# HT_L293D_Driver.net
KiCad netlist of a schematic drawn in Altium Designer
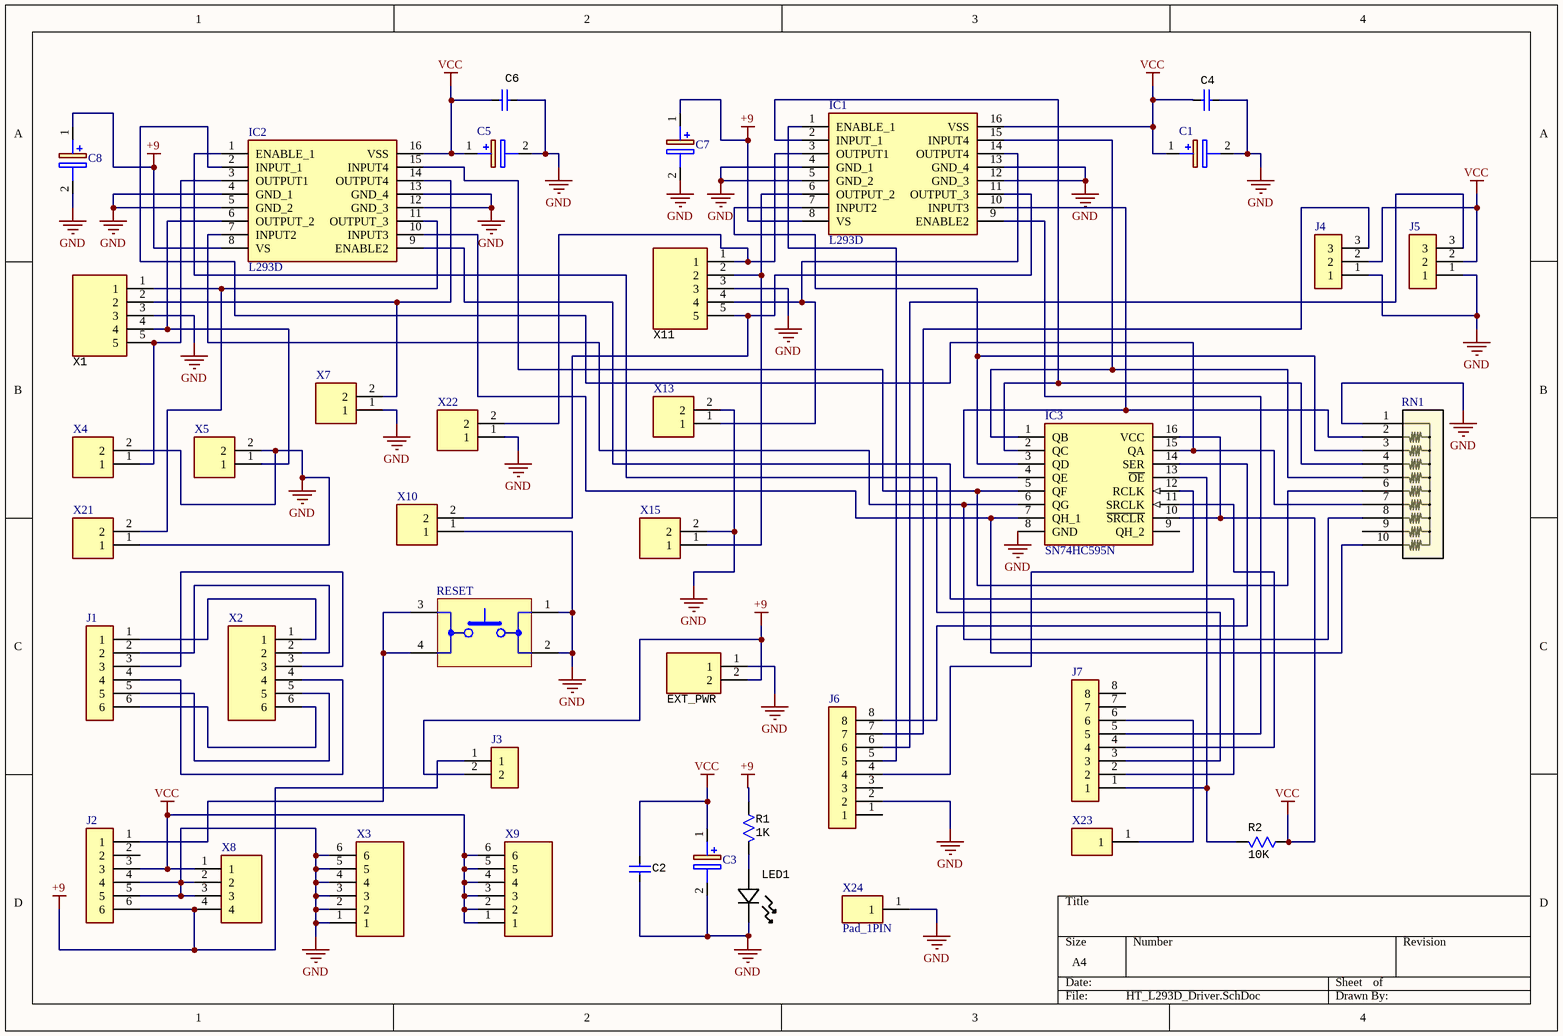
[diagram p0: HT_L293D_Driver.SchDoc]

(export (version "E")
  (design (tool "Eeschema 10.0.6"))
  (components
    (comp (ref "C1")
      (value "Aluminum_Electrolytic_Capacitor")
      (footprint "Aluminum_Electrolytic_Capacitor")
      (description "Capacitor Polarised")
      (fields (field (name "MANUFACTURER_PART_NUMBER") "EKY-350ETC221MH15D") (field (name "VOLTAGE") "100uF"))
      (libsource (lib "") (part "Aluminum_Electrolytic_Capacitor_1"))
    )
    (comp (ref "C2")
      (value "~")
      (footprint "CERAMIC_CAPACITOR_0.1uF")
      (fields
        (field (name "MANUFACTURER") "Epcos")
        (field (name "PARTNUMBER") "B32774D4106K000")
        (field (name "VALUEMANUFACTURERPARTNUMBER") "Film capacitor, 10μF, 450VDC, ±10%, 10.9mOhm, 31.5x15 mm, -40...+105°C")
      )
      (libsource (lib "MyL293D") (part "Ceramic_Capacitor"))
    )
    (comp (ref "C3")
      (value "Aluminum_Electrolytic_Capacitor")
      (footprint "Aluminum_Electrolytic_Capacitor")
      (description "Capacitor Polarised")
      (fields (field (name "MANUFACTURER_PART_NUMBER") "EKY-350ETC221MH15D") (field (name "VOLTAGE") "16VDC"))
      (libsource (lib "MyL293D") (part "Aluminum_Electrolytic_Capacitor"))
    )
    (comp (ref "C4")
      (value "~")
      (footprint "CERAMIC_CAPACITOR_0.1uF")
      (description "Capacitor Non Polarised")
      (fields (field (name "MANUFACTURER") "Epcos") (field (name "PARTNUMBER") "B32774D4106K000"))
      (libsource (lib "MyL293D") (part "Ceramic_Capacitor"))
    )
    (comp (ref "C5")
      (value "Aluminum_Electrolytic_Capacitor")
      (footprint "Aluminum_Electrolytic_Capacitor")
      (description "Capacitor Polarised")
      (fields (field (name "MANUFACTURER_PART_NUMBER") "EKY-350ETC221MH15D") (field (name "VOLTAGE") "16VDC"))
      (libsource (lib "") (part "Aluminum_Electrolytic_Capacitor_1"))
    )
    (comp (ref "C6")
      (value "~")
      (footprint "CERAMIC_CAPACITOR_0.1uF")
      (fields
        (field (name "MANUFACTURER") "Epcos")
        (field (name "PARTNUMBER") "B32774D4106K000")
        (field (name "VALUEMANUFACTURERPARTNUMBER") "Film capacitor, 0.1μF, 450VDC, ±10%, 10.9mOhm, 31.5x15 mm, -40...+105°C")
      )
      (libsource (lib "MyL293D") (part "Ceramic_Capacitor"))
    )
    (comp (ref "C7")
      (value "Aluminum_Electrolytic_Capacitor")
      (footprint "Aluminum_Electrolytic_Capacitor")
      (description "Capacitor Polarised")
      (fields (field (name "MANUFACTURER_PART_NUMBER") "EKY-350ETC221MH15D") (field (name "VOLTAGE") "16VDC"))
      (libsource (lib "MyL293D") (part "Aluminum_Electrolytic_Capacitor"))
    )
    (comp (ref "C8")
      (value "Aluminum_Electrolytic_Capacitor")
      (footprint "Aluminum_Electrolytic_Capacitor")
      (description "Capacitor Polarised")
      (fields (field (name "MANUFACTURER_PART_NUMBER") "EKY-350ETC221MH15D") (field (name "VOLTAGE") "16VDC"))
      (libsource (lib "MyL293D") (part "Aluminum_Electrolytic_Capacitor"))
    )
    (comp (ref "EXT_PWR")
      (value "~")
      (footprint "Terminal_Block_2PIN")
      (fields
        (field (name "MANUFACTURER") "Degson")
        (field (name "VALUEMANUFACTURERPARTNUMBER") "Terminal connector, 2pin, 3.5mm, 300VAC, 10A")
        (field (name "PARTNUMBER") "DG350-3.5-02P-14")
      )
      (libsource (lib "MyL293D") (part "Terminal_Block_2PIN"))
    )
    (comp (ref "IC1")
      (value "L293D")
      (footprint "L293D_WITH_DIP16")
      (description "Integrated Circuit")
      (fields (field (name "MOUSER PART NUMBER") "511-L293D"))
      (libsource (lib "MyL293D") (part "L293D"))
    )
    (comp (ref "IC2")
      (value "L293D")
      (footprint "L293D_WITH_DIP16")
      (description "Integrated Circuit")
      (fields (field (name "MOUSER PART NUMBER") "511-L293D"))
      (libsource (lib "MyL293D") (part "L293D"))
    )
    (comp (ref "IC3")
      (value "SN74HC595N")
      (footprint "L293D_WITH_DIP16")
      (description "Integrated Circuit")
      (fields (field (name "MOUSER PART NUMBER") "595-SN74HC595N"))
      (libsource (lib "MyL293D") (part "SN74HC595N"))
    )
    (comp (ref "J1")
      (value "Headers_6PIN")
      (footprint "HEADERS_6PIN")
      (fields (field (name "MF") "{'manufacturer': u'TE Connectivity'}") (field (name "MP") "87227-3"))
      (libsource (lib "MyL293D") (part "Headers_6PIN"))
    )
    (comp (ref "J2")
      (value "Headers_6PIN")
      (footprint "HEADERS_6PIN")
      (fields (field (name "MF") "{'manufacturer': u'TE Connectivity'}") (field (name "MP") "87227-3"))
      (libsource (lib "MyL293D") (part "Headers_6PIN"))
    )
    (comp (ref "J3")
      (value "Headers_2PIN")
      (footprint "HEADERS_2PIN")
      (fields (field (name "MF") "{'manufacturer': u'TE Connectivity'}") (field (name "MP") "87227-3"))
      (libsource (lib "MyL293D") (part "Headers_2PIN"))
    )
    (comp (ref "J4")
      (value "Headers_3PIN")
      (footprint "HEADERS_3PIN")
      (fields (field (name "MF") "{'manufacturer': u'TE Connectivity'}") (field (name "MP") "87227-3"))
      (libsource (lib "MyL293D") (part "Headers_3PIN"))
    )
    (comp (ref "J5")
      (value "Headers_3PIN")
      (footprint "HEADERS_3PIN")
      (fields (field (name "MF") "{'manufacturer': u'TE Connectivity'}") (field (name "MP") "87227-3"))
      (libsource (lib "MyL293D") (part "Headers_3PIN"))
    )
    (comp (ref "J6")
      (value "Headers_8PIN")
      (footprint "HEADERS_8PIN")
      (fields (field (name "MF") "{'manufacturer': u'TE Connectivity'}") (field (name "MP") "87227-3"))
      (libsource (lib "MyL293D") (part "Headers_8PIN"))
    )
    (comp (ref "J7")
      (value "Headers_8PIN")
      (footprint "HEADERS_8PIN")
      (fields (field (name "MF") "{'manufacturer': u'TE Connectivity'}") (field (name "MP") "87227-3"))
      (libsource (lib "MyL293D") (part "Headers_8PIN"))
    )
    (comp (ref "LED1")
      (value "~")
      (footprint "Green_LED_3mm")
      (fields (field (name "VALUEMANUFACTURERPARTNUMBER") "LED, Green, *, *, *, -55...+150°C"))
      (libsource (lib "MyL293D") (part "Green_LED_3mm"))
    )
    (comp (ref "R1")
      (value "1K")
      (footprint "RESISTOR_TH_1K")
      (fields
        (field (name "MANUFACTURER") "Yageo")
        (field (name "PARTNUMBER") "RC0201JR-07100RL")
        (field (name "VALUEMANUFACTURERPARTNUMBER") "Resistor film, 1K, , 0201, 0.05W, -55...+125°C")
      )
      (libsource (lib "MyL293D") (part "Resistor_1K"))
    )
    (comp (ref "R2")
      (value "10K")
      (footprint "RESISTOR_TH_10K")
      (fields
        (field (name "MANUFACTURER") "Yageo")
        (field (name "PARTNUMBER") "RC0201JR-07100RL")
        (field (name "VALUEMANUFACTURERPARTNUMBER") "Resistor film, 10K, , 0201, 0.05W, -55...+125°C")
      )
      (libsource (lib "MyL293D") (part "Resistor_10K"))
    )
    (comp (ref "RESET")
      (value "1825910-6")
      (footprint "1825910-6")
      (description "SWITCH TACTILE SPST-NO 0.05A 24V")
      (fields
        (field (name "MANUFACTURER") "TE Connectivity")
        (field (name ".CREATOR") "MM")
        (field (name ".CHECKED PCB") "RF")
        (field (name ".CHECKED SCH") "RF")
      )
      (libsource (lib "MyL293D") (part "Button_Reset"))
    )
    (comp (ref "RN1")
      (value "Resistor_Network_10K")
      (footprint "RESISTOR_NETWORK_10K")
      (libsource (lib "MyL293D") (part "Resistor_Network_10K"))
    )
    (comp (ref "X1")
      (value "~")
      (footprint "TERMINAL_BLOCK_5PIN")
      (fields
        (field (name "MANUFACTURER") "Degson")
        (field (name "VALUEMANUFACTURERPARTNUMBER") "Terminal connector, 3pin, 3.5mm, 300VAC, 10A")
        (field (name "PARTNUMBER") "DG350-3.5-03P-14")
      )
      (libsource (lib "MyL293D") (part "Terminal_Block_5PIN"))
    )
    (comp (ref "X2") (value "Pad_6PIN") (footprint "PAD_6PIN") (libsource (lib "") (part "Pad_6PIN_1")))
    (comp (ref "X3") (value "Pad_6PIN") (footprint "PAD_6PIN") (libsource (lib "MyL293D") (part "Pad_6PIN")))
    (comp (ref "X4") (value "Pad_2PIN") (footprint "PAD_2PIN") (libsource (lib "MyL293D") (part "Pad_2PIN")))
    (comp (ref "X5") (value "Pad_2PIN") (footprint "PAD_2PIN") (libsource (lib "MyL293D") (part "Pad_2PIN")))
    (comp (ref "X7") (value "Pad_2PIN") (footprint "PAD_2PIN") (libsource (lib "MyL293D") (part "Pad_2PIN")))
    (comp (ref "X8") (value "Pad_4PIN") (footprint "PAD_4PIN") (libsource (lib "MyL293D") (part "Pad_4PIN")))
    (comp (ref "X9") (value "Pad_6PIN") (footprint "PAD_6PIN") (libsource (lib "MyL293D") (part "Pad_6PIN")))
    (comp (ref "X10") (value "Pad_2PIN") (footprint "PAD_2PIN") (libsource (lib "MyL293D") (part "Pad_2PIN")))
    (comp (ref "X11")
      (value "~")
      (footprint "TERMINAL_BLOCK_5PIN")
      (fields
        (field (name "MANUFACTURER") "Degson")
        (field (name "VALUEMANUFACTURERPARTNUMBER") "Terminal connector, 3pin, 3.5mm, 300VAC, 10A")
        (field (name "PARTNUMBER") "DG350-3.5-03P-14")
      )
      (libsource (lib "MyL293D") (part "Terminal_Block_5PIN"))
    )
    (comp (ref "X13") (value "Pad_2PIN") (footprint "PAD_2PIN") (libsource (lib "MyL293D") (part "Pad_2PIN")))
    (comp (ref "X15") (value "Pad_2PIN") (footprint "PAD_2PIN") (libsource (lib "MyL293D") (part "Pad_2PIN")))
    (comp (ref "X21") (value "Pad_2PIN") (footprint "PAD_2PIN") (libsource (lib "MyL293D") (part "Pad_2PIN")))
    (comp (ref "X22") (value "Pad_2PIN") (footprint "PAD_2PIN") (libsource (lib "MyL293D") (part "Pad_2PIN")))
    (comp (ref "X23") (value "Pad_1PIN") (footprint "PAD_1PIN") (libsource (lib "MyL293D") (part "Pad_1PIN")))
    (comp (ref "X24") (value "Pad_1PIN") (footprint "PAD_1PIN") (libsource (lib "MyL293D") (part "Pad_1PIN")))
  )
  (nets
    (net (code "1") (name "+9") (class "Default")
      (node (ref "C7") (pin "1") (pinfunction "+_1") (pintype "passive"))
      (node (ref "C8") (pin "1") (pinfunction "+_1") (pintype "passive"))
      (node (ref "EXT_PWR") (pin "2") (pinfunction "2_2") (pintype "passive"))
      (node (ref "IC1") (pin "8") (pinfunction "VS_8") (pintype "passive"))
      (node (ref "IC2") (pin "8") (pinfunction "VS_8") (pintype "passive"))
      (node (ref "J2") (pin "6") (pinfunction "6_6") (pintype "passive"))
      (node (ref "J3") (pin "1") (pinfunction "1_1") (pintype "passive"))
      (node (ref "J3") (pin "2") (pinfunction "2_2") (pintype "passive"))
      (node (ref "R1") (pin "1") (pinfunction "1_1") (pintype "passive"))
      (node (ref "X8") (pin "4") (pinfunction "4_4") (pintype "passive"))
    )
    (net (code "2") (name "GND") (class "Default")
      (node (ref "C1") (pin "2") (pinfunction "-_2") (pintype "passive"))
      (node (ref "C2") (pin "2") (pinfunction "2_2") (pintype "passive"))
      (node (ref "C3") (pin "2") (pinfunction "-_2") (pintype "passive"))
      (node (ref "C4") (pin "2") (pinfunction "2_2") (pintype "passive"))
      (node (ref "C5") (pin "2") (pinfunction "-_2") (pintype "passive"))
      (node (ref "C6") (pin "2") (pinfunction "2_2") (pintype "passive"))
      (node (ref "C7") (pin "2") (pinfunction "-_2") (pintype "passive"))
      (node (ref "C8") (pin "2") (pinfunction "-_2") (pintype "passive"))
      (node (ref "EXT_PWR") (pin "1") (pinfunction "1_1") (pintype "passive"))
      (node (ref "IC1") (pin "12") (pinfunction "GND_3_12") (pintype "passive"))
      (node (ref "IC1") (pin "13") (pinfunction "GND_4_13") (pintype "passive"))
      (node (ref "IC1") (pin "4") (pinfunction "GND_1_4") (pintype "passive"))
      (node (ref "IC1") (pin "5") (pinfunction "GND_2_5") (pintype "passive"))
      (node (ref "IC2") (pin "12") (pinfunction "GND_3_12") (pintype "passive"))
      (node (ref "IC2") (pin "13") (pinfunction "GND_4_13") (pintype "passive"))
      (node (ref "IC2") (pin "4") (pinfunction "GND_1_4") (pintype "passive"))
      (node (ref "IC2") (pin "5") (pinfunction "GND_2_5") (pintype "passive"))
      (node (ref "IC3") (pin "8") (pinfunction "GND_8") (pintype "power_in"))
      (node (ref "J2") (pin "4") (pinfunction "4_4") (pintype "passive"))
      (node (ref "J2") (pin "5") (pinfunction "5_5") (pintype "passive"))
      (node (ref "J4") (pin "1") (pinfunction "1_1") (pintype "passive"))
      (node (ref "J5") (pin "1") (pinfunction "1_1") (pintype "passive"))
      (node (ref "J6") (pin "2") (pinfunction "2_2") (pintype "passive"))
      (node (ref "LED1") (pin "1") (pinfunction "1_1") (pintype "passive"))
      (node (ref "RESET") (pin "1") (pinfunction "1_1") (pintype "passive"))
      (node (ref "RESET") (pin "2") (pinfunction "2_2") (pintype "passive"))
      (node (ref "RN1") (pin "1") (pinfunction "1_1") (pintype "passive"))
      (node (ref "X1") (pin "3") (pinfunction "3_3") (pintype "passive"))
      (node (ref "X10") (pin "1") (pinfunction "1_1") (pintype "passive"))
      (node (ref "X11") (pin "3") (pinfunction "3_3") (pintype "passive"))
      (node (ref "X13") (pin "2") (pinfunction "2_2") (pintype "passive"))
      (node (ref "X15") (pin "2") (pinfunction "2_2") (pintype "passive"))
      (node (ref "X21") (pin "1") (pinfunction "1_1") (pintype "passive"))
      (node (ref "X22") (pin "1") (pinfunction "1_1") (pintype "passive"))
      (node (ref "X24") (pin "1") (pinfunction "1_1") (pintype "passive"))
      (node (ref "X3") (pin "1") (pinfunction "1_1") (pintype "passive"))
      (node (ref "X3") (pin "2") (pinfunction "2_2") (pintype "passive"))
      (node (ref "X3") (pin "3") (pinfunction "3_3") (pintype "passive"))
      (node (ref "X3") (pin "4") (pinfunction "4_4") (pintype "passive"))
      (node (ref "X3") (pin "5") (pinfunction "5_5") (pintype "passive"))
      (node (ref "X3") (pin "6") (pinfunction "6_6") (pintype "passive"))
      (node (ref "X4") (pin "2") (pinfunction "2_2") (pintype "passive"))
      (node (ref "X5") (pin "2") (pinfunction "2_2") (pintype "passive"))
      (node (ref "X7") (pin "1") (pinfunction "1_1") (pintype "passive"))
      (node (ref "X8") (pin "2") (pinfunction "2_2") (pintype "passive"))
      (node (ref "X8") (pin "3") (pinfunction "3_3") (pintype "passive"))
    )
    (net (code "3") (name "Net-(IC1-ENABLE2)") (class "Default")
      (node (ref "IC1") (pin "9") (pinfunction "ENABLE2_9") (pintype "passive"))
      (node (ref "J7") (pin "5") (pinfunction "5_5") (pintype "passive"))
    )
    (net (code "4") (name "Net-(IC1-ENABLE_1)") (class "Default")
      (node (ref "IC1") (pin "1") (pinfunction "ENABLE_1_1") (pintype "passive"))
      (node (ref "J6") (pin "5") (pinfunction "5_5") (pintype "passive"))
    )
    (net (code "5") (name "Net-(IC1-INPUT2)") (class "Default")
      (node (ref "IC1") (pin "7") (pinfunction "INPUT2_7") (pintype "passive"))
      (node (ref "IC3") (pin "3") (pinfunction "QD_3") (pintype "passive"))
      (node (ref "RN1") (pin "3") (pinfunction "3_3") (pintype "passive"))
    )
    (net (code "6") (name "Net-(IC1-INPUT3)") (class "Default")
      (node (ref "IC1") (pin "10") (pinfunction "INPUT3_10") (pintype "passive"))
      (node (ref "IC3") (pin "4") (pinfunction "QE_4") (pintype "passive"))
      (node (ref "RN1") (pin "2") (pinfunction "2_2") (pintype "passive"))
    )
    (net (code "7") (name "Net-(IC1-INPUT4)") (class "Default")
      (node (ref "IC1") (pin "15") (pinfunction "INPUT4_15") (pintype "passive"))
      (node (ref "IC3") (pin "1") (pinfunction "QB_1") (pintype "passive"))
      (node (ref "RN1") (pin "5") (pinfunction "5_5") (pintype "passive"))
    )
    (net (code "8") (name "Net-(IC1-INPUT_1)") (class "Default")
      (node (ref "IC1") (pin "2") (pinfunction "INPUT_1_2") (pintype "passive"))
      (node (ref "IC3") (pin "2") (pinfunction "QC_2") (pintype "passive"))
      (node (ref "RN1") (pin "4") (pinfunction "4_4") (pintype "passive"))
    )
    (net (code "9") (name "Net-(IC1-OUTPUT1)") (class "Default")
      (node (ref "IC1") (pin "3") (pinfunction "OUTPUT1_3") (pintype "passive"))
      (node (ref "X11") (pin "1") (pinfunction "1_1") (pintype "passive"))
      (node (ref "X22") (pin "2") (pinfunction "2_2") (pintype "passive"))
    )
    (net (code "10") (name "Net-(IC1-OUTPUT4)") (class "Default")
      (node (ref "IC1") (pin "14") (pinfunction "OUTPUT4_14") (pintype "passive"))
      (node (ref "X11") (pin "4") (pinfunction "4_4") (pintype "passive"))
      (node (ref "X13") (pin "1") (pinfunction "1_1") (pintype "passive"))
    )
    (net (code "11") (name "Net-(IC1-OUTPUT_2)") (class "Default")
      (node (ref "IC1") (pin "6") (pinfunction "OUTPUT_2_6") (pintype "passive"))
      (node (ref "X11") (pin "2") (pinfunction "2_2") (pintype "passive"))
      (node (ref "X15") (pin "1") (pinfunction "1_1") (pintype "passive"))
    )
    (net (code "12") (name "Net-(IC1-OUTPUT_3)") (class "Default")
      (node (ref "IC1") (pin "11") (pinfunction "OUTPUT_3_11") (pintype "passive"))
      (node (ref "X10") (pin "2") (pinfunction "2_2") (pintype "passive"))
      (node (ref "X11") (pin "5") (pinfunction "5_5") (pintype "passive"))
    )
    (net (code "13") (name "Net-(IC2-ENABLE2)") (class "Default")
      (node (ref "IC2") (pin "9") (pinfunction "ENABLE2_9") (pintype "passive"))
      (node (ref "J7") (pin "2") (pinfunction "2_2") (pintype "passive"))
    )
    (net (code "14") (name "Net-(IC2-ENABLE_1)") (class "Default")
      (node (ref "IC2") (pin "1") (pinfunction "ENABLE_1_1") (pintype "passive"))
      (node (ref "J7") (pin "3") (pinfunction "3_3") (pintype "passive"))
    )
    (net (code "15") (name "Net-(IC2-INPUT2)") (class "Default")
      (node (ref "IC2") (pin "7") (pinfunction "INPUT2_7") (pintype "passive"))
      (node (ref "IC3") (pin "6") (pinfunction "QG_6") (pintype "passive"))
      (node (ref "RN1") (pin "8") (pinfunction "8_8") (pintype "passive"))
    )
    (net (code "16") (name "Net-(IC2-INPUT3)") (class "Default")
      (node (ref "IC2") (pin "10") (pinfunction "INPUT3_10") (pintype "passive"))
      (node (ref "IC3") (pin "7") (pinfunction "QH_1_7") (pintype "passive"))
      (node (ref "RN1") (pin "10") (pinfunction "10_10") (pintype "passive"))
    )
    (net (code "17") (name "Net-(IC2-INPUT4)") (class "Default")
      (node (ref "IC2") (pin "15") (pinfunction "INPUT4_15") (pintype "passive"))
      (node (ref "IC3") (pin "5") (pinfunction "QF_5") (pintype "passive"))
      (node (ref "RN1") (pin "6") (pinfunction "6_6") (pintype "passive"))
    )
    (net (code "18") (name "Net-(IC2-INPUT_1)") (class "Default")
      (node (ref "IC2") (pin "2") (pinfunction "INPUT_1_2") (pintype "passive"))
      (node (ref "IC3") (pin "15") (pinfunction "QA_15") (pintype "passive"))
      (node (ref "RN1") (pin "7") (pinfunction "7_7") (pintype "passive"))
    )
    (net (code "19") (name "Net-(IC2-OUTPUT1)") (class "Default")
      (node (ref "IC2") (pin "3") (pinfunction "OUTPUT1_3") (pintype "passive"))
      (node (ref "X1") (pin "5") (pinfunction "5_5") (pintype "passive"))
      (node (ref "X4") (pin "1") (pinfunction "1_1") (pintype "passive"))
    )
    (net (code "20") (name "Net-(IC2-OUTPUT4)") (class "Default")
      (node (ref "IC2") (pin "14") (pinfunction "OUTPUT4_14") (pintype "passive"))
      (node (ref "X1") (pin "2") (pinfunction "2_2") (pintype "passive"))
      (node (ref "X7") (pin "2") (pinfunction "2_2") (pintype "passive"))
    )
    (net (code "21") (name "Net-(IC2-OUTPUT_2)") (class "Default")
      (node (ref "IC2") (pin "6") (pinfunction "OUTPUT_2_6") (pintype "passive"))
      (node (ref "X1") (pin "4") (pinfunction "4_4") (pintype "passive"))
      (node (ref "X5") (pin "1") (pinfunction "1_1") (pintype "passive"))
    )
    (net (code "22") (name "Net-(IC2-OUTPUT_3)") (class "Default")
      (node (ref "IC2") (pin "11") (pinfunction "OUTPUT_3_11") (pintype "passive"))
      (node (ref "X1") (pin "1") (pinfunction "1_1") (pintype "passive"))
      (node (ref "X21") (pin "2") (pinfunction "2_2") (pintype "passive"))
    )
    (net (code "23") (name "Net-(IC3-RCLK)") (class "Default")
      (node (ref "IC3") (pin "12") (pinfunction "RCLK_12") (pintype "input"))
      (node (ref "J6") (pin "4") (pinfunction "4_4") (pintype "passive"))
    )
    (net (code "24") (name "Net-(IC3-SER)") (class "Default")
      (node (ref "IC3") (pin "14") (pinfunction "SER_14") (pintype "passive"))
      (node (ref "J6") (pin "8") (pinfunction "8_8") (pintype "passive"))
    )
    (net (code "25") (name "Net-(IC3-SRCLK)") (class "Default")
      (node (ref "IC3") (pin "11") (pinfunction "SRCLK_11") (pintype "input"))
      (node (ref "J7") (pin "4") (pinfunction "4_4") (pintype "passive"))
    )
    (net (code "26") (name "Net-(IC3-~{OE})") (class "Default")
      (node (ref "IC3") (pin "13") (pinfunction "~{OE}_13") (pintype "passive"))
      (node (ref "J7") (pin "1") (pinfunction "1_1") (pintype "passive"))
      (node (ref "R2") (pin "2") (pinfunction "2_2") (pintype "passive"))
    )
    (net (code "27") (name "Net-(J1-Pad1)") (class "Default")
      (node (ref "J1") (pin "1") (pinfunction "1_1") (pintype "passive"))
      (node (ref "X2") (pin "1") (pinfunction "1_1") (pintype "passive"))
    )
    (net (code "28") (name "Net-(J1-Pad2)") (class "Default")
      (node (ref "J1") (pin "2") (pinfunction "2_2") (pintype "passive"))
      (node (ref "X2") (pin "2") (pinfunction "2_2") (pintype "passive"))
    )
    (net (code "29") (name "Net-(J1-Pad3)") (class "Default")
      (node (ref "J1") (pin "3") (pinfunction "3_3") (pintype "passive"))
      (node (ref "X2") (pin "3") (pinfunction "3_3") (pintype "passive"))
    )
    (net (code "30") (name "Net-(J1-Pad4)") (class "Default")
      (node (ref "J1") (pin "4") (pinfunction "4_4") (pintype "passive"))
      (node (ref "X2") (pin "4") (pinfunction "4_4") (pintype "passive"))
    )
    (net (code "31") (name "Net-(J1-Pad5)") (class "Default")
      (node (ref "J1") (pin "5") (pinfunction "5_5") (pintype "passive"))
      (node (ref "X2") (pin "5") (pinfunction "5_5") (pintype "passive"))
    )
    (net (code "32") (name "Net-(J1-Pad6)") (class "Default")
      (node (ref "J1") (pin "6") (pinfunction "6_6") (pintype "passive"))
      (node (ref "X2") (pin "6") (pinfunction "6_6") (pintype "passive"))
    )
    (net (code "33") (name "Net-(J4-Pad3)") (class "Default")
      (node (ref "J4") (pin "3") (pinfunction "3_3") (pintype "passive"))
      (node (ref "J6") (pin "7") (pinfunction "7_7") (pintype "passive"))
    )
    (net (code "34") (name "Net-(J5-Pad3)") (class "Default")
      (node (ref "J5") (pin "3") (pinfunction "3_3") (pintype "passive"))
      (node (ref "J6") (pin "6") (pinfunction "6_6") (pintype "passive"))
    )
    (net (code "35") (name "Net-(J7-Pad6)") (class "Default")
      (node (ref "J7") (pin "6") (pinfunction "6_6") (pintype "passive"))
      (node (ref "X23") (pin "1") (pinfunction "1_1") (pintype "passive"))
    )
    (net (code "36") (name "Net-(LED1-Pad2)") (class "Default")
      (node (ref "LED1") (pin "2") (pinfunction "2_2") (pintype "passive"))
      (node (ref "R1") (pin "2") (pinfunction "2_2") (pintype "passive"))
    )
    (net (code "37") (name "Net-(RESET-MECH1)") (class "Default")
      (node (ref "J2") (pin "1") (pinfunction "1_1") (pintype "passive"))
      (node (ref "RESET") (pin "3") (pinfunction "MECH1_3") (pintype "passive"))
      (node (ref "RESET") (pin "4") (pinfunction "MECH2_4") (pintype "passive"))
    )
    (net (code "38") (name "VCC") (class "Default")
      (node (ref "C1") (pin "1") (pinfunction "+_1") (pintype "passive"))
      (node (ref "C2") (pin "1") (pinfunction "1_1") (pintype "passive"))
      (node (ref "C3") (pin "1") (pinfunction "+_1") (pintype "passive"))
      (node (ref "C4") (pin "1") (pinfunction "1_1") (pintype "passive"))
      (node (ref "C5") (pin "1") (pinfunction "+_1") (pintype "passive"))
      (node (ref "C6") (pin "1") (pinfunction "1_1") (pintype "passive"))
      (node (ref "IC1") (pin "16") (pinfunction "VSS_16") (pintype "passive"))
      (node (ref "IC2") (pin "16") (pinfunction "VSS_16") (pintype "passive"))
      (node (ref "IC3") (pin "10") (pinfunction "~{SRCLR}_10") (pintype "passive"))
      (node (ref "IC3") (pin "16") (pinfunction "VCC_16") (pintype "power_in"))
      (node (ref "J2") (pin "3") (pinfunction "3_3") (pintype "passive"))
      (node (ref "J4") (pin "2") (pinfunction "2_2") (pintype "passive"))
      (node (ref "J5") (pin "2") (pinfunction "2_2") (pintype "passive"))
      (node (ref "R2") (pin "1") (pinfunction "1_1") (pintype "passive"))
      (node (ref "X8") (pin "1") (pinfunction "1_1") (pintype "passive"))
      (node (ref "X9") (pin "1") (pinfunction "1_1") (pintype "passive"))
      (node (ref "X9") (pin "2") (pinfunction "2_2") (pintype "passive"))
      (node (ref "X9") (pin "3") (pinfunction "3_3") (pintype "passive"))
      (node (ref "X9") (pin "4") (pinfunction "4_4") (pintype "passive"))
      (node (ref "X9") (pin "5") (pinfunction "5_5") (pintype "passive"))
      (node (ref "X9") (pin "6") (pinfunction "6_6") (pintype "passive"))
    )
    (net (code "39") (name "unconnected-(IC3-QH_2-Pad9)") (class "Default")
      (node (ref "IC3") (pin "9") (pinfunction "QH_2_9") (pintype "passive"))
    )
    (net (code "40") (name "unconnected-(J2-Pad2)") (class "Default")
      (node (ref "J2") (pin "2") (pinfunction "2_2") (pintype "passive"))
    )
    (net (code "41") (name "unconnected-(J6-Pad1)") (class "Default")
      (node (ref "J6") (pin "1") (pinfunction "1_1") (pintype "passive"))
    )
    (net (code "42") (name "unconnected-(J6-Pad3)") (class "Default")
      (node (ref "J6") (pin "3") (pinfunction "3_3") (pintype "passive"))
    )
    (net (code "43") (name "unconnected-(J7-Pad7)") (class "Default")
      (node (ref "J7") (pin "7") (pinfunction "7_7") (pintype "passive"))
    )
    (net (code "44") (name "unconnected-(J7-Pad8)") (class "Default")
      (node (ref "J7") (pin "8") (pinfunction "8_8") (pintype "passive"))
    )
    (net (code "45") (name "unconnected-(RN1-Pad9)") (class "Default")
      (node (ref "RN1") (pin "9") (pinfunction "9_9") (pintype "passive"))
    )
  )
)
